# double100tqfp.net
KiCad netlist of a schematic drawn in EAGLE
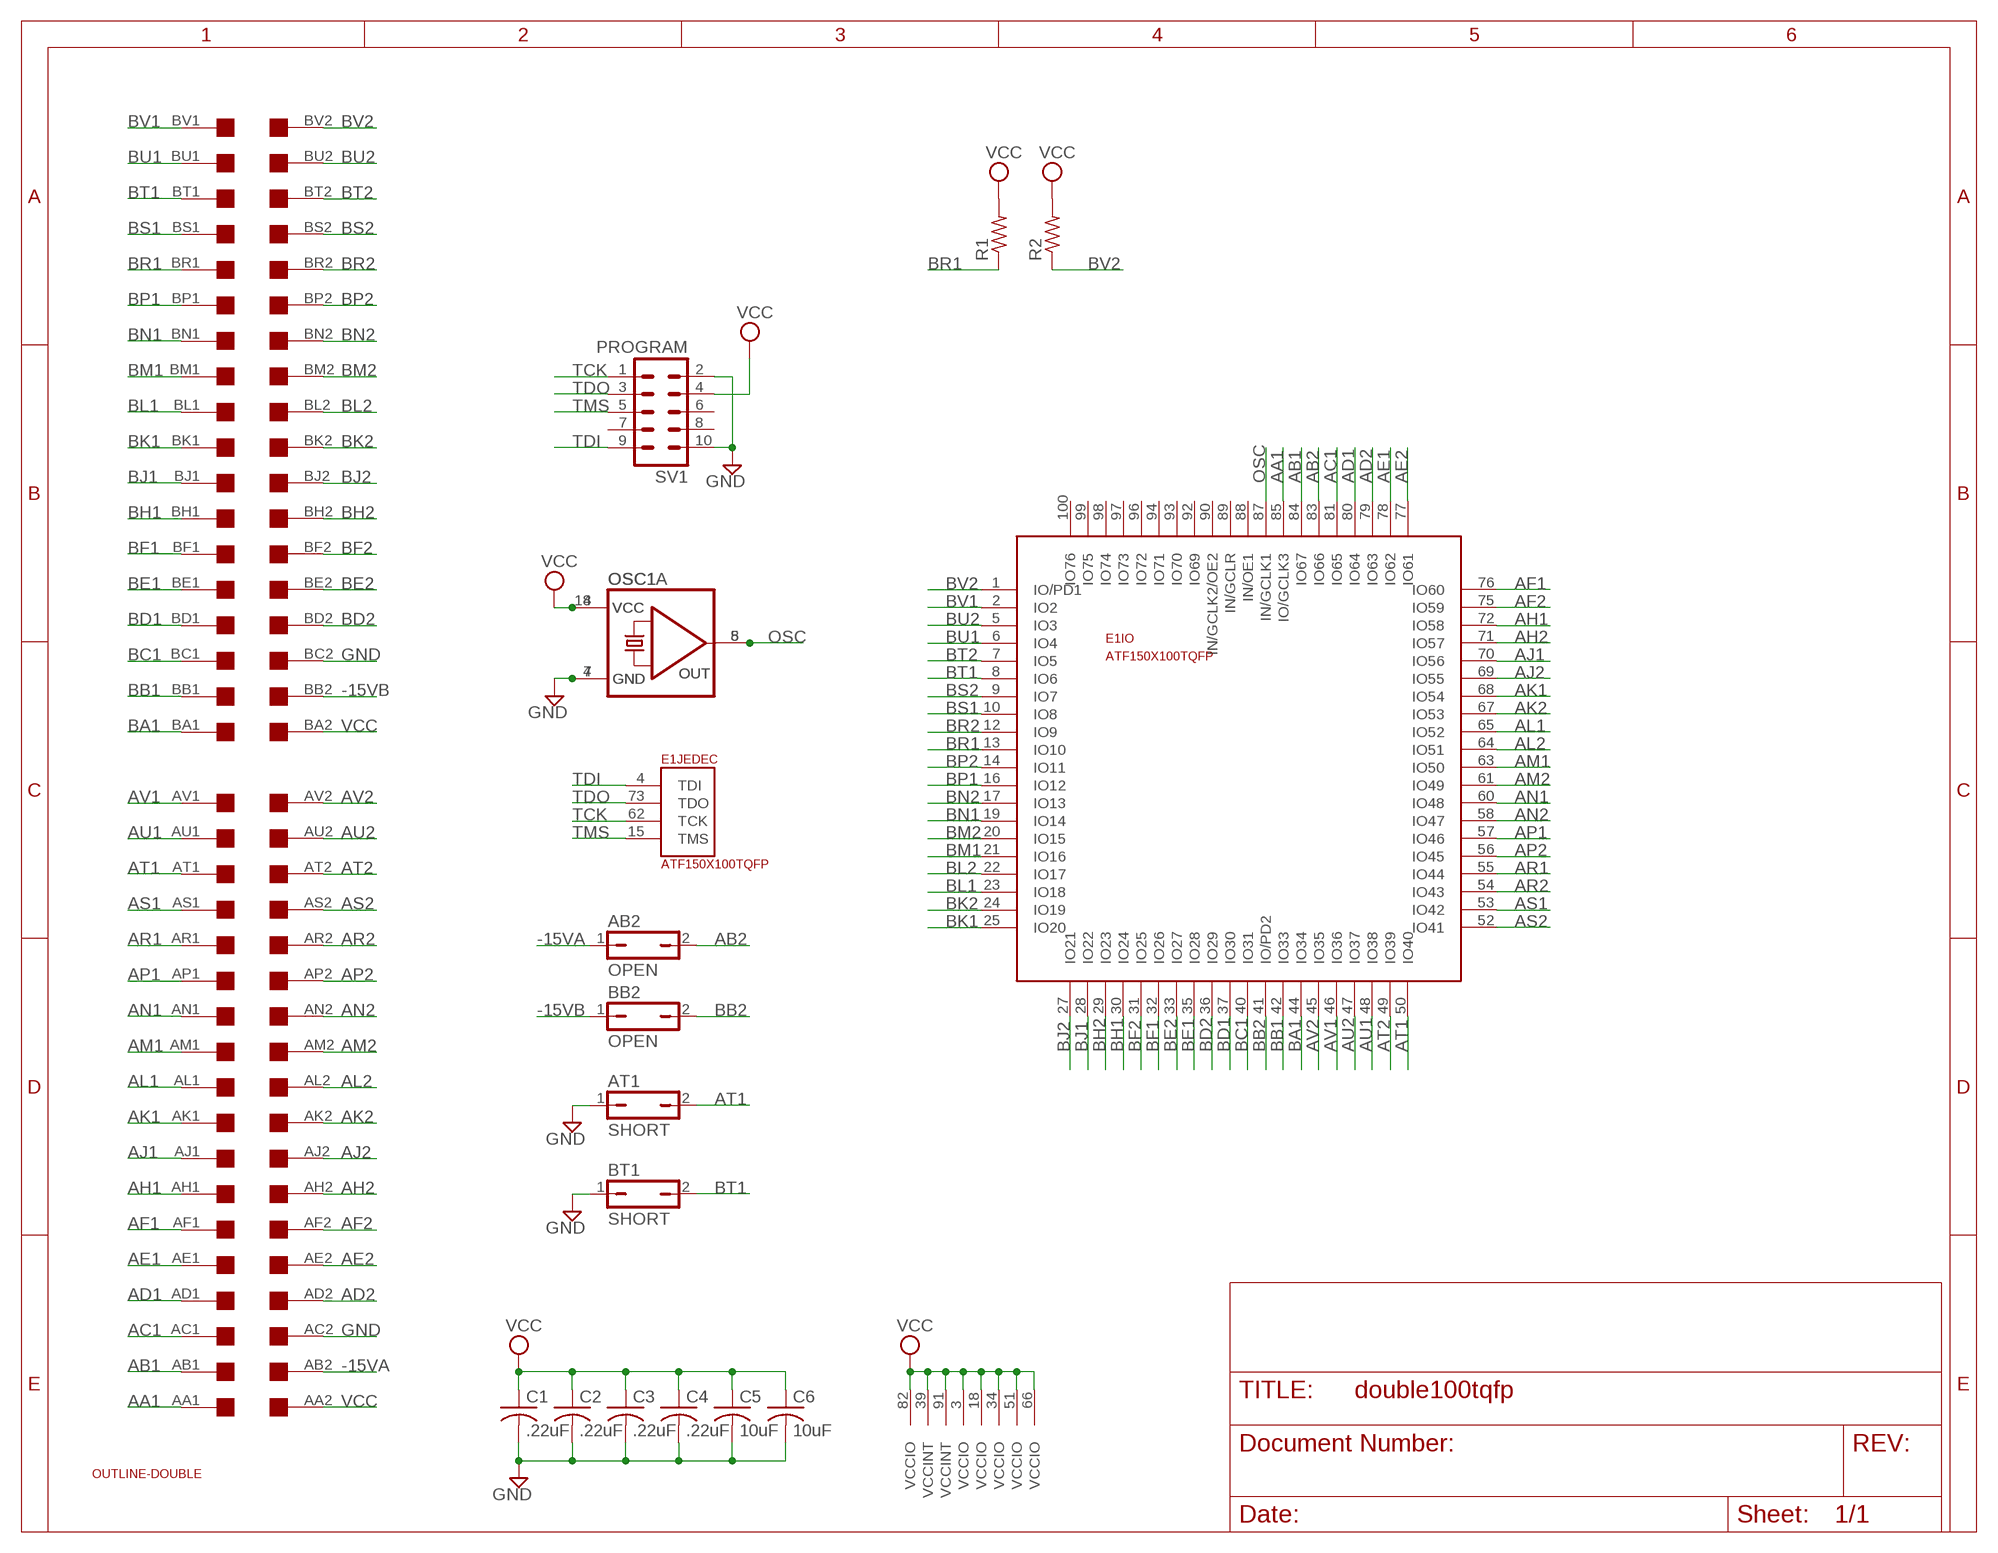
[diagram p0: schematic, sheet 1]

(export (version "E")
  (design (tool "Eeschema 10.0.6"))
  (components
    (comp (ref "AB2")
      (value "OPEN")
      (footprint "eagle-import:JP1")
      (libsource (lib "eagle-import") (part "JP1Q"))
    )
    (comp (ref "AT1")
      (value "SHORT")
      (footprint "eagle-import:JP1")
      (libsource (lib "eagle-import") (part "JP1Q"))
    )
    (comp (ref "BB2")
      (value "OPEN")
      (footprint "eagle-import:JP1")
      (libsource (lib "eagle-import") (part "JP1Q"))
    )
    (comp (ref "BT1")
      (value "SHORT")
      (footprint "eagle-import:JP1")
      (libsource (lib "eagle-import") (part "JP1Q"))
    )
    (comp (ref "C1")
      (value ".22uF")
      (footprint "eagle-import:C0805")
      (libsource (lib "eagle-import") (part "C-USC0805"))
    )
    (comp (ref "C2")
      (value ".22uF")
      (footprint "eagle-import:C0805")
      (libsource (lib "eagle-import") (part "C-USC0805"))
    )
    (comp (ref "C3")
      (value ".22uF")
      (footprint "eagle-import:C0805")
      (libsource (lib "eagle-import") (part "C-USC0805"))
    )
    (comp (ref "C4")
      (value ".22uF")
      (footprint "eagle-import:C0805")
      (libsource (lib "eagle-import") (part "C-USC0805"))
    )
    (comp (ref "C5")
      (value "10uF")
      (footprint "eagle-import:C0805")
      (libsource (lib "eagle-import") (part "C-USC0805"))
    )
    (comp (ref "C6")
      (value "10uF")
      (footprint "eagle-import:C0805")
      (libsource (lib "eagle-import") (part "C-USC0805"))
    )
    (comp (ref "E1")
      (value "ATF150X100TQFP")
      (footprint "eagle-import:TQFP-100")
      (libsource (lib "eagle-import") (part "ATF150X100TQFP"))
    )
    (comp (ref "OSC1")
      (value "QG5460")
      (footprint "eagle-import:DIL08S")
      (libsource (lib "eagle-import") (part "QG5460"))
    )
    (comp (ref "OSC1A")
      (value "QG5860")
      (footprint "eagle-import:DIL14S")
      (libsource (lib "eagle-import") (part "QG5860"))
    )
    (comp (ref "R1")
      (value "R-US_0207/10")
      (footprint "eagle-import:0207_10")
      (libsource (lib "eagle-import") (part "R-US_0207/10"))
    )
    (comp (ref "R2")
      (value "R-US_0207/10")
      (footprint "eagle-import:0207_10")
      (libsource (lib "eagle-import") (part "R-US_0207/10"))
    )
    (comp (ref "SV1")
      (value "PROGRAM")
      (footprint "eagle-import:ML10")
      (libsource (lib "eagle-import") (part "ML10"))
    )
    (comp (ref "U$1")
      (value "DOUBLE")
      (footprint "eagle-import:EDGE-CON4")
      (libsource (lib "eagle-import") (part "DOUBLE"))
    )
    (comp (ref "U$3")
      (value "OUTLINE-DOUBLE")
      (footprint "eagle-import:DOUBLE")
      (libsource (lib "eagle-import") (part "OUTLINE-DOUBLE"))
    )
  )
  (nets
    (net (code "1") (name "/-15VA") (class "Default")
      (node (ref "AB2") (pin "1") (pinfunction "1_1") (pintype "passive"))
      (node (ref "U$1") (pin "AB2") (pinfunction "1_AB2") (pintype "bidirectional"))
    )
    (net (code "2") (name "/-15VB") (class "Default")
      (node (ref "BB2") (pin "1") (pinfunction "1_1") (pintype "passive"))
      (node (ref "U$1") (pin "BB2") (pinfunction "1_BB2") (pintype "bidirectional"))
    )
    (net (code "3") (name "/AA1") (class "Default")
      (node (ref "E1") (pin "85") (pinfunction "IO/GCLK3_85") (pintype "bidirectional"))
      (node (ref "U$1") (pin "AA1") (pinfunction "1_AA1") (pintype "bidirectional"))
    )
    (net (code "4") (name "/AB1") (class "Default")
      (node (ref "E1") (pin "84") (pinfunction "IO67_84") (pintype "bidirectional"))
      (node (ref "U$1") (pin "AB1") (pinfunction "1_AB1") (pintype "bidirectional"))
    )
    (net (code "5") (name "/AB2") (class "Default")
      (node (ref "AB2") (pin "2") (pinfunction "2_2") (pintype "passive"))
      (node (ref "E1") (pin "83") (pinfunction "IO66_83") (pintype "bidirectional"))
    )
    (net (code "6") (name "/AC1") (class "Default")
      (node (ref "E1") (pin "81") (pinfunction "IO65_81") (pintype "bidirectional"))
      (node (ref "U$1") (pin "AC1") (pinfunction "1_AC1") (pintype "bidirectional"))
    )
    (net (code "7") (name "/AD1") (class "Default")
      (node (ref "E1") (pin "80") (pinfunction "IO64_80") (pintype "bidirectional"))
      (node (ref "U$1") (pin "AD1") (pinfunction "1_AD1") (pintype "bidirectional"))
    )
    (net (code "8") (name "/AD2") (class "Default")
      (node (ref "E1") (pin "79") (pinfunction "IO63_79") (pintype "bidirectional"))
      (node (ref "U$1") (pin "AD2") (pinfunction "1_AD2") (pintype "bidirectional"))
    )
    (net (code "9") (name "/AE1") (class "Default")
      (node (ref "E1") (pin "78") (pinfunction "IO62_78") (pintype "bidirectional"))
      (node (ref "U$1") (pin "AE1") (pinfunction "1_AE1") (pintype "bidirectional"))
    )
    (net (code "10") (name "/AE2") (class "Default")
      (node (ref "E1") (pin "77") (pinfunction "IO61_77") (pintype "bidirectional"))
      (node (ref "U$1") (pin "AE2") (pinfunction "1_AE2") (pintype "bidirectional"))
    )
    (net (code "11") (name "/AF1") (class "Default")
      (node (ref "E1") (pin "76") (pinfunction "IO60_76") (pintype "bidirectional"))
      (node (ref "U$1") (pin "AF1") (pinfunction "1_AF1") (pintype "bidirectional"))
    )
    (net (code "12") (name "/AF2") (class "Default")
      (node (ref "E1") (pin "75") (pinfunction "IO59_75") (pintype "bidirectional"))
      (node (ref "U$1") (pin "AF2") (pinfunction "1_AF2") (pintype "bidirectional"))
    )
    (net (code "13") (name "/AH1") (class "Default")
      (node (ref "E1") (pin "72") (pinfunction "IO58_72") (pintype "bidirectional"))
      (node (ref "U$1") (pin "AH1") (pinfunction "1_AH1") (pintype "bidirectional"))
    )
    (net (code "14") (name "/AH2") (class "Default")
      (node (ref "E1") (pin "71") (pinfunction "IO57_71") (pintype "bidirectional"))
      (node (ref "U$1") (pin "AH2") (pinfunction "1_AH2") (pintype "bidirectional"))
    )
    (net (code "15") (name "/AJ1") (class "Default")
      (node (ref "E1") (pin "70") (pinfunction "IO56_70") (pintype "bidirectional"))
      (node (ref "U$1") (pin "AJ1") (pinfunction "1_AJ1") (pintype "bidirectional"))
    )
    (net (code "16") (name "/AJ2") (class "Default")
      (node (ref "E1") (pin "69") (pinfunction "IO55_69") (pintype "bidirectional"))
      (node (ref "U$1") (pin "AJ2") (pinfunction "1_AJ2") (pintype "bidirectional"))
    )
    (net (code "17") (name "/AK1") (class "Default")
      (node (ref "E1") (pin "68") (pinfunction "IO54_68") (pintype "bidirectional"))
      (node (ref "U$1") (pin "AK1") (pinfunction "1_AK1") (pintype "bidirectional"))
    )
    (net (code "18") (name "/AK2") (class "Default")
      (node (ref "E1") (pin "67") (pinfunction "IO53_67") (pintype "bidirectional"))
      (node (ref "U$1") (pin "AK2") (pinfunction "1_AK2") (pintype "bidirectional"))
    )
    (net (code "19") (name "/AL1") (class "Default")
      (node (ref "E1") (pin "65") (pinfunction "IO52_65") (pintype "bidirectional"))
      (node (ref "U$1") (pin "AL1") (pinfunction "1_AL1") (pintype "bidirectional"))
    )
    (net (code "20") (name "/AL2") (class "Default")
      (node (ref "E1") (pin "64") (pinfunction "IO51_64") (pintype "bidirectional"))
      (node (ref "U$1") (pin "AL2") (pinfunction "1_AL2") (pintype "bidirectional"))
    )
    (net (code "21") (name "/AM1") (class "Default")
      (node (ref "E1") (pin "63") (pinfunction "IO50_63") (pintype "bidirectional"))
      (node (ref "U$1") (pin "AM1") (pinfunction "1_AM1") (pintype "bidirectional"))
    )
    (net (code "22") (name "/AM2") (class "Default")
      (node (ref "E1") (pin "61") (pinfunction "IO49_61") (pintype "bidirectional"))
      (node (ref "U$1") (pin "AM2") (pinfunction "1_AM2") (pintype "bidirectional"))
    )
    (net (code "23") (name "/AN1") (class "Default")
      (node (ref "E1") (pin "60") (pinfunction "IO48_60") (pintype "bidirectional"))
      (node (ref "U$1") (pin "AN1") (pinfunction "1_AN1") (pintype "bidirectional"))
    )
    (net (code "24") (name "/AN2") (class "Default")
      (node (ref "E1") (pin "58") (pinfunction "IO47_58") (pintype "bidirectional"))
      (node (ref "U$1") (pin "AN2") (pinfunction "1_AN2") (pintype "bidirectional"))
    )
    (net (code "25") (name "/AP1") (class "Default")
      (node (ref "E1") (pin "57") (pinfunction "IO46_57") (pintype "bidirectional"))
      (node (ref "U$1") (pin "AP1") (pinfunction "1_AP1") (pintype "bidirectional"))
    )
    (net (code "26") (name "/AP2") (class "Default")
      (node (ref "E1") (pin "56") (pinfunction "IO45_56") (pintype "bidirectional"))
      (node (ref "U$1") (pin "AP2") (pinfunction "1_AP2") (pintype "bidirectional"))
    )
    (net (code "27") (name "/AR1") (class "Default")
      (node (ref "E1") (pin "55") (pinfunction "IO44_55") (pintype "bidirectional"))
      (node (ref "U$1") (pin "AR1") (pinfunction "1_AR1") (pintype "bidirectional"))
    )
    (net (code "28") (name "/AR2") (class "Default")
      (node (ref "E1") (pin "54") (pinfunction "IO43_54") (pintype "bidirectional"))
      (node (ref "U$1") (pin "AR2") (pinfunction "1_AR2") (pintype "bidirectional"))
    )
    (net (code "29") (name "/AS1") (class "Default")
      (node (ref "E1") (pin "53") (pinfunction "IO42_53") (pintype "bidirectional"))
      (node (ref "U$1") (pin "AS1") (pinfunction "1_AS1") (pintype "bidirectional"))
    )
    (net (code "30") (name "/AS2") (class "Default")
      (node (ref "E1") (pin "52") (pinfunction "IO41_52") (pintype "bidirectional"))
      (node (ref "U$1") (pin "AS2") (pinfunction "1_AS2") (pintype "bidirectional"))
    )
    (net (code "31") (name "/AT1") (class "Default")
      (node (ref "AT1") (pin "2") (pinfunction "2_2") (pintype "passive"))
      (node (ref "E1") (pin "50") (pinfunction "IO40_50") (pintype "bidirectional"))
      (node (ref "U$1") (pin "AT1") (pinfunction "1_AT1") (pintype "bidirectional"))
    )
    (net (code "32") (name "/AT2") (class "Default")
      (node (ref "E1") (pin "49") (pinfunction "IO39_49") (pintype "bidirectional"))
      (node (ref "U$1") (pin "AT2") (pinfunction "1_AT2") (pintype "bidirectional"))
    )
    (net (code "33") (name "/AU1") (class "Default")
      (node (ref "E1") (pin "48") (pinfunction "IO38_48") (pintype "bidirectional"))
      (node (ref "U$1") (pin "AU1") (pinfunction "1_AU1") (pintype "bidirectional"))
    )
    (net (code "34") (name "/AU2") (class "Default")
      (node (ref "E1") (pin "47") (pinfunction "IO37_47") (pintype "bidirectional"))
      (node (ref "U$1") (pin "AU2") (pinfunction "1_AU2") (pintype "bidirectional"))
    )
    (net (code "35") (name "/AV1") (class "Default")
      (node (ref "E1") (pin "46") (pinfunction "IO36_46") (pintype "bidirectional"))
      (node (ref "U$1") (pin "AV1") (pinfunction "1_AV1") (pintype "bidirectional"))
    )
    (net (code "36") (name "/AV2") (class "Default")
      (node (ref "E1") (pin "45") (pinfunction "IO35_45") (pintype "bidirectional"))
      (node (ref "U$1") (pin "AV2") (pinfunction "1_AV2") (pintype "bidirectional"))
    )
    (net (code "37") (name "/BA1") (class "Default")
      (node (ref "E1") (pin "44") (pinfunction "IO34_44") (pintype "bidirectional"))
      (node (ref "U$1") (pin "BA1") (pinfunction "1_BA1") (pintype "bidirectional"))
    )
    (net (code "38") (name "/BB1") (class "Default")
      (node (ref "E1") (pin "42") (pinfunction "IO33_42") (pintype "bidirectional"))
      (node (ref "U$1") (pin "BB1") (pinfunction "1_BB1") (pintype "bidirectional"))
    )
    (net (code "39") (name "/BB2") (class "Default")
      (node (ref "BB2") (pin "2") (pinfunction "2_2") (pintype "passive"))
      (node (ref "E1") (pin "41") (pinfunction "IO/PD2_41") (pintype "bidirectional"))
    )
    (net (code "40") (name "/BC1") (class "Default")
      (node (ref "E1") (pin "40") (pinfunction "IO31_40") (pintype "bidirectional"))
      (node (ref "U$1") (pin "BC1") (pinfunction "1_BC1") (pintype "bidirectional"))
    )
    (net (code "41") (name "/BD1") (class "Default")
      (node (ref "E1") (pin "37") (pinfunction "IO30_37") (pintype "bidirectional"))
      (node (ref "U$1") (pin "BD1") (pinfunction "1_BD1") (pintype "bidirectional"))
    )
    (net (code "42") (name "/BD2") (class "Default")
      (node (ref "E1") (pin "36") (pinfunction "IO29_36") (pintype "bidirectional"))
      (node (ref "U$1") (pin "BD2") (pinfunction "1_BD2") (pintype "bidirectional"))
    )
    (net (code "43") (name "/BE1") (class "Default")
      (node (ref "E1") (pin "35") (pinfunction "IO28_35") (pintype "bidirectional"))
      (node (ref "U$1") (pin "BE1") (pinfunction "1_BE1") (pintype "bidirectional"))
    )
    (net (code "44") (name "/BE2") (class "Default")
      (node (ref "E1") (pin "33") (pinfunction "IO27_33") (pintype "bidirectional"))
      (node (ref "U$1") (pin "BE2") (pinfunction "1_BE2") (pintype "bidirectional"))
    )
    (net (code "45") (name "/BF1") (class "Default")
      (node (ref "E1") (pin "32") (pinfunction "IO26_32") (pintype "bidirectional"))
      (node (ref "U$1") (pin "BF1") (pinfunction "1_BF1") (pintype "bidirectional"))
    )
    (net (code "46") (name "/BF2") (class "Default")
      (node (ref "E1") (pin "31") (pinfunction "IO25_31") (pintype "bidirectional"))
      (node (ref "U$1") (pin "BF2") (pinfunction "1_BF2") (pintype "bidirectional"))
    )
    (net (code "47") (name "/BH1") (class "Default")
      (node (ref "E1") (pin "30") (pinfunction "IO24_30") (pintype "bidirectional"))
      (node (ref "U$1") (pin "BH1") (pinfunction "1_BH1") (pintype "bidirectional"))
    )
    (net (code "48") (name "/BH2") (class "Default")
      (node (ref "E1") (pin "29") (pinfunction "IO23_29") (pintype "bidirectional"))
      (node (ref "U$1") (pin "BH2") (pinfunction "1_BH2") (pintype "bidirectional"))
    )
    (net (code "49") (name "/BJ1") (class "Default")
      (node (ref "E1") (pin "28") (pinfunction "IO22_28") (pintype "bidirectional"))
      (node (ref "U$1") (pin "BJ1") (pinfunction "1_BJ1") (pintype "bidirectional"))
    )
    (net (code "50") (name "/BJ2") (class "Default")
      (node (ref "E1") (pin "27") (pinfunction "IO21_27") (pintype "bidirectional"))
      (node (ref "U$1") (pin "BJ2") (pinfunction "1_BJ2") (pintype "bidirectional"))
    )
    (net (code "51") (name "/BK1") (class "Default")
      (node (ref "E1") (pin "25") (pinfunction "IO20_25") (pintype "bidirectional"))
      (node (ref "U$1") (pin "BK1") (pinfunction "1_BK1") (pintype "bidirectional"))
    )
    (net (code "52") (name "/BK2") (class "Default")
      (node (ref "E1") (pin "24") (pinfunction "IO19_24") (pintype "bidirectional"))
      (node (ref "U$1") (pin "BK2") (pinfunction "1_BK2") (pintype "bidirectional"))
    )
    (net (code "53") (name "/BL1") (class "Default")
      (node (ref "E1") (pin "23") (pinfunction "IO18_23") (pintype "bidirectional"))
      (node (ref "U$1") (pin "BL1") (pinfunction "1_BL1") (pintype "bidirectional"))
    )
    (net (code "54") (name "/BL2") (class "Default")
      (node (ref "E1") (pin "22") (pinfunction "IO17_22") (pintype "bidirectional"))
      (node (ref "U$1") (pin "BL2") (pinfunction "1_BL2") (pintype "bidirectional"))
    )
    (net (code "55") (name "/BM1") (class "Default")
      (node (ref "E1") (pin "21") (pinfunction "IO16_21") (pintype "bidirectional"))
      (node (ref "U$1") (pin "BM1") (pinfunction "1_BM1") (pintype "bidirectional"))
    )
    (net (code "56") (name "/BM2") (class "Default")
      (node (ref "E1") (pin "20") (pinfunction "IO15_20") (pintype "bidirectional"))
      (node (ref "U$1") (pin "BM2") (pinfunction "1_BM2") (pintype "bidirectional"))
    )
    (net (code "57") (name "/BN1") (class "Default")
      (node (ref "E1") (pin "19") (pinfunction "IO14_19") (pintype "bidirectional"))
      (node (ref "U$1") (pin "BN1") (pinfunction "1_BN1") (pintype "bidirectional"))
    )
    (net (code "58") (name "/BN2") (class "Default")
      (node (ref "E1") (pin "17") (pinfunction "IO13_17") (pintype "bidirectional"))
      (node (ref "U$1") (pin "BN2") (pinfunction "1_BN2") (pintype "bidirectional"))
    )
    (net (code "59") (name "/BP1") (class "Default")
      (node (ref "E1") (pin "16") (pinfunction "IO12_16") (pintype "bidirectional"))
      (node (ref "U$1") (pin "BP1") (pinfunction "1_BP1") (pintype "bidirectional"))
    )
    (net (code "60") (name "/BP2") (class "Default")
      (node (ref "E1") (pin "14") (pinfunction "IO11_14") (pintype "bidirectional"))
      (node (ref "U$1") (pin "BP2") (pinfunction "1_BP2") (pintype "bidirectional"))
    )
    (net (code "61") (name "/BR1") (class "Default")
      (node (ref "E1") (pin "13") (pinfunction "IO10_13") (pintype "bidirectional"))
      (node (ref "R1") (pin "1") (pinfunction "1_1") (pintype "passive"))
      (node (ref "U$1") (pin "BR1") (pinfunction "1_BR1") (pintype "bidirectional"))
    )
    (net (code "62") (name "/BR2") (class "Default")
      (node (ref "E1") (pin "12") (pinfunction "IO9_12") (pintype "bidirectional"))
      (node (ref "U$1") (pin "BR2") (pinfunction "1_BR2") (pintype "bidirectional"))
    )
    (net (code "63") (name "/BS1") (class "Default")
      (node (ref "E1") (pin "10") (pinfunction "IO8_10") (pintype "bidirectional"))
      (node (ref "U$1") (pin "BS1") (pinfunction "1_BS1") (pintype "bidirectional"))
    )
    (net (code "64") (name "/BS2") (class "Default")
      (node (ref "E1") (pin "9") (pinfunction "IO7_9") (pintype "bidirectional"))
      (node (ref "U$1") (pin "BS2") (pinfunction "1_BS2") (pintype "bidirectional"))
    )
    (net (code "65") (name "/BT1") (class "Default")
      (node (ref "BT1") (pin "2") (pinfunction "2_2") (pintype "passive"))
      (node (ref "E1") (pin "8") (pinfunction "IO6_8") (pintype "bidirectional"))
      (node (ref "U$1") (pin "BT1") (pinfunction "1_BT1") (pintype "bidirectional"))
    )
    (net (code "66") (name "/BT2") (class "Default")
      (node (ref "E1") (pin "7") (pinfunction "IO5_7") (pintype "bidirectional"))
      (node (ref "U$1") (pin "BT2") (pinfunction "1_BT2") (pintype "bidirectional"))
    )
    (net (code "67") (name "/BU1") (class "Default")
      (node (ref "E1") (pin "6") (pinfunction "IO4_6") (pintype "bidirectional"))
      (node (ref "U$1") (pin "BU1") (pinfunction "1_BU1") (pintype "bidirectional"))
    )
    (net (code "68") (name "/BU2") (class "Default")
      (node (ref "E1") (pin "5") (pinfunction "IO3_5") (pintype "bidirectional"))
      (node (ref "U$1") (pin "BU2") (pinfunction "1_BU2") (pintype "bidirectional"))
    )
    (net (code "69") (name "/BV1") (class "Default")
      (node (ref "E1") (pin "2") (pinfunction "IO2_2") (pintype "bidirectional"))
      (node (ref "U$1") (pin "BV1") (pinfunction "1_BV1") (pintype "bidirectional"))
    )
    (net (code "70") (name "/BV2") (class "Default")
      (node (ref "E1") (pin "1") (pinfunction "IO/PD1_1") (pintype "bidirectional"))
      (node (ref "R2") (pin "1") (pinfunction "1_1") (pintype "passive"))
      (node (ref "U$1") (pin "BV2") (pinfunction "1_BV2") (pintype "bidirectional"))
    )
    (net (code "71") (name "/OSC") (class "Default")
      (node (ref "E1") (pin "87") (pinfunction "IN/GCLK1_87") (pintype "input"))
      (node (ref "OSC1") (pin "5") (pinfunction "OUT_5") (pintype "output"))
      (node (ref "OSC1A") (pin "8") (pinfunction "OUT_8") (pintype "output"))
    )
    (net (code "72") (name "/TCK") (class "Default")
      (node (ref "E1") (pin "62") (pinfunction "TCK_62") (pintype "bidirectional"))
      (node (ref "SV1") (pin "1") (pinfunction "1_1") (pintype "passive"))
    )
    (net (code "73") (name "/TDI") (class "Default")
      (node (ref "E1") (pin "4") (pinfunction "TDI_4") (pintype "bidirectional"))
      (node (ref "SV1") (pin "9") (pinfunction "9_9") (pintype "passive"))
    )
    (net (code "74") (name "/TDO") (class "Default")
      (node (ref "E1") (pin "73") (pinfunction "TDO_73") (pintype "bidirectional"))
      (node (ref "SV1") (pin "3") (pinfunction "3_3") (pintype "passive"))
    )
    (net (code "75") (name "/TMS") (class "Default")
      (node (ref "E1") (pin "15") (pinfunction "TMS_15") (pintype "bidirectional"))
      (node (ref "SV1") (pin "5") (pinfunction "5_5") (pintype "passive"))
    )
    (net (code "76") (name "GND") (class "Default")
      (node (ref "AT1") (pin "1") (pinfunction "1_1") (pintype "passive"))
      (node (ref "BT1") (pin "1") (pinfunction "1_1") (pintype "passive"))
      (node (ref "C1") (pin "2") (pinfunction "2_2") (pintype "passive"))
      (node (ref "C2") (pin "2") (pinfunction "2_2") (pintype "passive"))
      (node (ref "C3") (pin "2") (pinfunction "2_2") (pintype "passive"))
      (node (ref "C4") (pin "2") (pinfunction "2_2") (pintype "passive"))
      (node (ref "C5") (pin "2") (pinfunction "2_2") (pintype "passive"))
      (node (ref "C6") (pin "2") (pinfunction "2_2") (pintype "passive"))
      (node (ref "OSC1") (pin "4") (pinfunction "GND_4") (pintype "power_in"))
      (node (ref "OSC1A") (pin "7") (pinfunction "GND_7") (pintype "power_in"))
      (node (ref "SV1") (pin "10") (pinfunction "10_10") (pintype "passive"))
      (node (ref "SV1") (pin "2") (pinfunction "2_2") (pintype "passive"))
      (node (ref "U$1") (pin "AC2") (pinfunction "1_AC2") (pintype "bidirectional"))
      (node (ref "U$1") (pin "BC2") (pinfunction "1_BC2") (pintype "bidirectional"))
    )
    (net (code "77") (name "VCC") (class "Default")
      (node (ref "C1") (pin "1") (pinfunction "1_1") (pintype "passive"))
      (node (ref "C2") (pin "1") (pinfunction "1_1") (pintype "passive"))
      (node (ref "C3") (pin "1") (pinfunction "1_1") (pintype "passive"))
      (node (ref "C4") (pin "1") (pinfunction "1_1") (pintype "passive"))
      (node (ref "C5") (pin "1") (pinfunction "1_1") (pintype "passive"))
      (node (ref "C6") (pin "1") (pinfunction "1_1") (pintype "passive"))
      (node (ref "E1") (pin "18") (pinfunction "VCCIO_18") (pintype "power_in"))
      (node (ref "E1") (pin "3") (pinfunction "VCCIO_3") (pintype "power_in"))
      (node (ref "E1") (pin "34") (pinfunction "VCCIO_34") (pintype "power_in"))
      (node (ref "E1") (pin "39") (pinfunction "VCCINT_39") (pintype "power_in"))
      (node (ref "E1") (pin "51") (pinfunction "VCCIO_51") (pintype "power_in"))
      (node (ref "E1") (pin "66") (pinfunction "VCCIO_66") (pintype "power_in"))
      (node (ref "E1") (pin "82") (pinfunction "VCCIO_82") (pintype "power_in"))
      (node (ref "E1") (pin "91") (pinfunction "VCCINT_91") (pintype "power_in"))
      (node (ref "OSC1") (pin "8") (pinfunction "VCC_8") (pintype "power_in"))
      (node (ref "OSC1A") (pin "14") (pinfunction "VCC_14") (pintype "power_in"))
      (node (ref "R1") (pin "2") (pinfunction "2_2") (pintype "passive"))
      (node (ref "R2") (pin "2") (pinfunction "2_2") (pintype "passive"))
      (node (ref "SV1") (pin "4") (pinfunction "4_4") (pintype "passive"))
      (node (ref "U$1") (pin "AA2") (pinfunction "1_AA2") (pintype "bidirectional"))
      (node (ref "U$1") (pin "BA2") (pinfunction "1_BA2") (pintype "bidirectional"))
    )
    (net (code "78") (name "unconnected-(E1Q-IN{slash}GCLK2{slash}OE2-Pad90)") (class "Default")
      (node (ref "E1") (pin "90") (pinfunction "IN/GCLK2/OE2_90") (pintype "input"))
    )
    (net (code "79") (name "unconnected-(E1Q-IN{slash}GCLR-Pad89)") (class "Default")
      (node (ref "E1") (pin "89") (pinfunction "IN/GCLR_89") (pintype "input"))
    )
    (net (code "80") (name "unconnected-(E1Q-IN{slash}OE1-Pad88)") (class "Default")
      (node (ref "E1") (pin "88") (pinfunction "IN/OE1_88") (pintype "input"))
    )
    (net (code "81") (name "unconnected-(E1Q-IO69-Pad92)") (class "Default")
      (node (ref "E1") (pin "92") (pinfunction "IO69_92") (pintype "bidirectional"))
    )
    (net (code "82") (name "unconnected-(E1Q-IO70-Pad93)") (class "Default")
      (node (ref "E1") (pin "93") (pinfunction "IO70_93") (pintype "bidirectional"))
    )
    (net (code "83") (name "unconnected-(E1Q-IO71-Pad94)") (class "Default")
      (node (ref "E1") (pin "94") (pinfunction "IO71_94") (pintype "bidirectional"))
    )
    (net (code "84") (name "unconnected-(E1Q-IO72-Pad96)") (class "Default")
      (node (ref "E1") (pin "96") (pinfunction "IO72_96") (pintype "bidirectional"))
    )
    (net (code "85") (name "unconnected-(E1Q-IO73-Pad97)") (class "Default")
      (node (ref "E1") (pin "97") (pinfunction "IO73_97") (pintype "bidirectional"))
    )
    (net (code "86") (name "unconnected-(E1Q-IO74-Pad98)") (class "Default")
      (node (ref "E1") (pin "98") (pinfunction "IO74_98") (pintype "bidirectional"))
    )
    (net (code "87") (name "unconnected-(E1Q-IO75-Pad99)") (class "Default")
      (node (ref "E1") (pin "99") (pinfunction "IO75_99") (pintype "bidirectional"))
    )
    (net (code "88") (name "unconnected-(E1Q-IO76-Pad100)") (class "Default")
      (node (ref "E1") (pin "100") (pinfunction "IO76_100") (pintype "bidirectional"))
    )
    (net (code "89") (name "unconnected-(SV1-Pad6)") (class "Default")
      (node (ref "SV1") (pin "6") (pinfunction "6_6") (pintype "passive"))
    )
    (net (code "90") (name "unconnected-(SV1-Pad7)") (class "Default")
      (node (ref "SV1") (pin "7") (pinfunction "7_7") (pintype "passive"))
    )
    (net (code "91") (name "unconnected-(SV1-Pad8)") (class "Default")
      (node (ref "SV1") (pin "8") (pinfunction "8_8") (pintype "passive"))
    )
  )
)
